# LPCB219_-_REMOTE_ACCEL_IF.net
KiCad netlist of a schematic drawn in Altium Designer
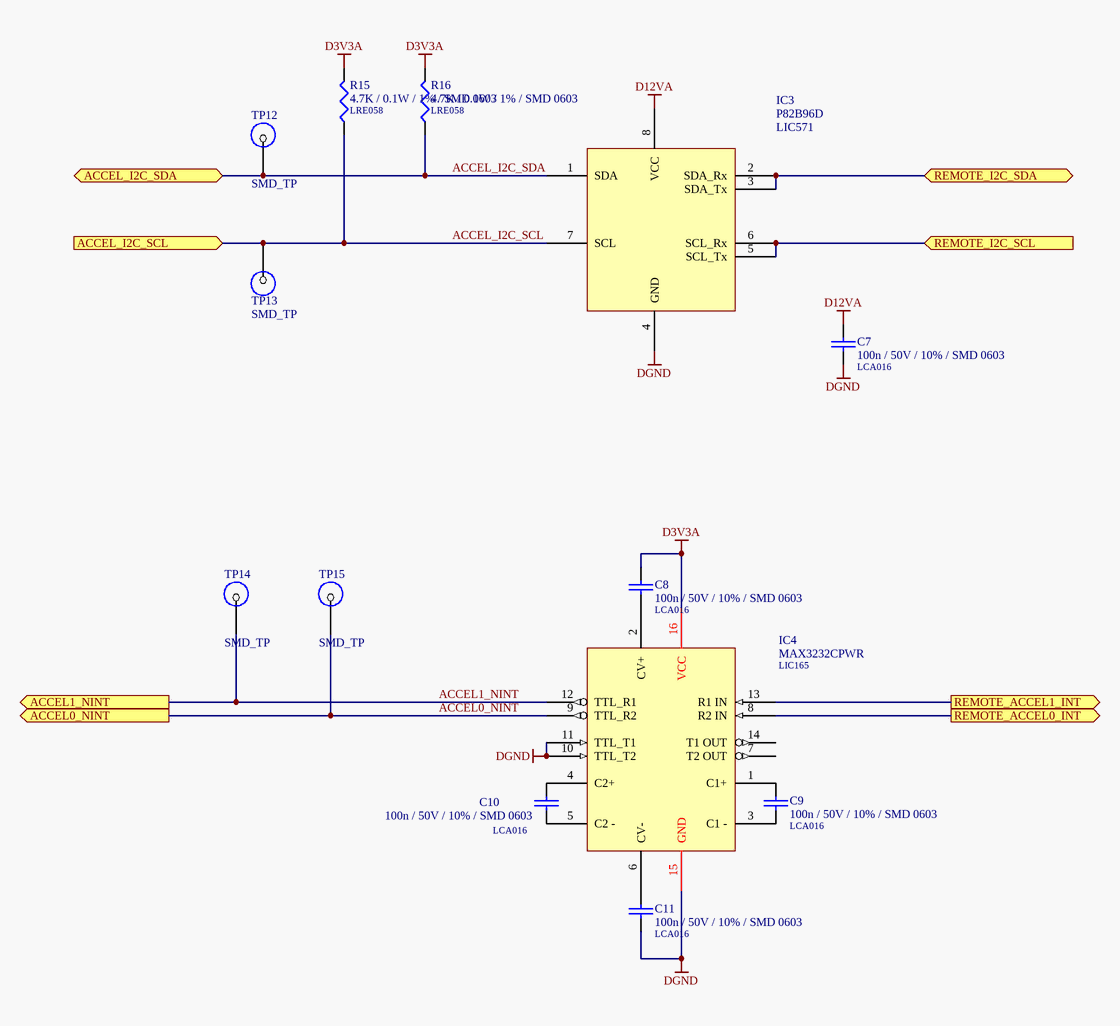
[diagram p0: LPCB219 - REMOTE ACCEL IF.SchDoc]

(export (version "E")
  (design (tool "Eeschema 10.0.6"))
  (components
    (comp (ref "C7")
      (value "100n / 50V / 10% / SMD 0603")
      (footprint "LFP011__CC1608-0603-IPC7351_B")
      (description "Capacitor, Ceramic Chip, 100nF (0.1uF), 50V, 5%, SMD 0603 [LCA016]")
      (fields (field (name "LDL_NUMBER") "LCA016"))
      (libsource (lib "LDL_Capacitors") (part "100n / 50V / 10% / SMD 0603"))
    )
    (comp (ref "C8")
      (value "100n / 50V / 10% / SMD 0603")
      (footprint "LFP011__CC1608-0603-IPC7351_B")
      (description "Capacitor, Ceramic Chip, 100nF, 50V, 10%, SMD 0603")
      (fields (field (name "LDL_NUMBER") "LCA016"))
      (libsource (lib "LDL_Capacitors") (part "100n / 50V / 10% / SMD 0603"))
    )
    (comp (ref "C9")
      (value "100n / 50V / 10% / SMD 0603")
      (footprint "LFP011__CC1608-0603-IPC7351_B")
      (description "Capacitor, Ceramic Chip, 100nF, 50V, 10%, SMD 0603")
      (fields (field (name "LDL_NUMBER") "LCA016"))
      (libsource (lib "LDL_Capacitors") (part "100n / 50V / 10% / SMD 0603"))
    )
    (comp (ref "C10")
      (value "100n / 50V / 10% / SMD 0603")
      (footprint "LFP011__CC1608-0603-IPC7351_B")
      (description "Capacitor, Ceramic Chip, 100nF, 50V, 10%, SMD 0603")
      (fields (field (name "LDL_NUMBER") "LCA016"))
      (libsource (lib "LDL_Capacitors") (part "100n / 50V / 10% / SMD 0603"))
    )
    (comp (ref "C11")
      (value "100n / 50V / 10% / SMD 0603")
      (footprint "LFP011__CC1608-0603-IPC7351_B")
      (description "Capacitor, Ceramic Chip, 100nF, 50V, 10%, SMD 0603")
      (fields (field (name "LDL_NUMBER") "LCA016"))
      (libsource (lib "LDL_Capacitors") (part "100n / 50V / 10% / SMD 0603"))
    )
    (comp (ref "IC3")
      (value "P82B96D")
      (footprint "LFP097__SOIC150-8")
      (description "IC, I2C Line Driver [LIC571]")
      (fields (field (name "LDL_NUMBER") "LIC571"))
      (libsource (lib "LDL_Semiconductors") (part "P82B96D"))
    )
    (comp (ref "IC4")
      (value "MAX3232CPWR")
      (footprint "LFP049__TSSOP-16")
      (description "IC, RS232 Line Driver, 3.3V, SMD TSSOP16")
      (fields (field (name "LDL_NUMBER") "LIC165"))
      (libsource (lib "LDL_Semiconductors") (part "MAX3232CPWR"))
    )
    (comp (ref "R15")
      (value "4.7K / 0.1W / 1% / SMD 0603")
      (footprint "LFP020__CR1608-0603-IPC7351_B")
      (description "Resistor, Ceramic Chip, 4K7, 0.1W, 1%, SMD 0603 [LRE058]")
      (fields (field (name "LDL_NUMBER") "LRE058"))
      (libsource (lib "LDL_Resistors") (part "4.7K / 0.1W / 1% / SMD 0603"))
    )
    (comp (ref "R16")
      (value "4.7K / 0.1W / 1% / SMD 0603")
      (footprint "LFP020__CR1608-0603-IPC7351_B")
      (description "Resistor, Ceramic Chip, 4K7, 0.1W, 1%, SMD 0603 [LRE058]")
      (fields (field (name "LDL_NUMBER") "LRE058"))
      (libsource (lib "LDL_Resistors") (part "4.7K / 0.1W / 1% / SMD 0603"))
    )
    (comp (ref "TP12")
      (value "SMD_TP")
      (footprint "SMD-TP")
      (description "SMD Test Point")
      (libsource (lib "LDL_Connectors") (part "SMD_TP"))
    )
    (comp (ref "TP13")
      (value "SMD_TP")
      (footprint "SMD-TP")
      (description "SMD Test Point")
      (libsource (lib "LDL_Connectors") (part "SMD_TP"))
    )
    (comp (ref "TP14")
      (value "SMD_TP")
      (footprint "SMD-TP")
      (description "SMD Test Point")
      (libsource (lib "LDL_Connectors") (part "SMD_TP"))
    )
    (comp (ref "TP15")
      (value "SMD_TP")
      (footprint "SMD-TP")
      (description "SMD Test Point")
      (libsource (lib "LDL_Connectors") (part "SMD_TP"))
    )
  )
  (nets
    (net (code "1") (name "/ACCEL0_NINT") (class "Default")
      (node (ref "IC4") (pin "9") (pinfunction "TTL_R2_9") (pintype "output"))
      (node (ref "TP15") (pin "1") (pintype "passive"))
    )
    (net (code "2") (name "/ACCEL1_NINT") (class "Default")
      (node (ref "IC4") (pin "12") (pinfunction "TTL_R1_12") (pintype "output"))
      (node (ref "TP14") (pin "1") (pintype "passive"))
    )
    (net (code "3") (name "/ACCEL_I2C_SCL") (class "Default")
      (node (ref "IC3") (pin "7") (pinfunction "SCL_7") (pintype "passive"))
      (node (ref "R15") (pin "1") (pintype "passive"))
      (node (ref "TP13") (pin "1") (pintype "passive"))
    )
    (net (code "4") (name "/ACCEL_I2C_SDA") (class "Default")
      (node (ref "IC3") (pin "1") (pinfunction "SDA_1") (pintype "passive"))
      (node (ref "R16") (pin "1") (pintype "passive"))
      (node (ref "TP12") (pin "1") (pintype "passive"))
    )
    (net (code "5") (name "/REMOTE_ACCEL0_INT") (class "Default")
      (node (ref "IC4") (pin "8") (pinfunction "R2_IN_8") (pintype "input"))
    )
    (net (code "6") (name "/REMOTE_ACCEL1_INT") (class "Default")
      (node (ref "IC4") (pin "13") (pinfunction "R1_IN_13") (pintype "input"))
    )
    (net (code "7") (name "/REMOTE_I2C_SCL") (class "Default")
      (node (ref "IC3") (pin "5") (pinfunction "SCL_Tx_5") (pintype "passive"))
      (node (ref "IC3") (pin "6") (pinfunction "SCL_Rx_6") (pintype "passive"))
    )
    (net (code "8") (name "/REMOTE_I2C_SDA") (class "Default")
      (node (ref "IC3") (pin "2") (pinfunction "SDA_Rx_2") (pintype "passive"))
      (node (ref "IC3") (pin "3") (pinfunction "SDA_Tx_3") (pintype "passive"))
    )
    (net (code "9") (name "D3V3A") (class "Default")
      (node (ref "C8") (pin "1") (pintype "passive"))
      (node (ref "IC4") (pin "16") (pinfunction "VCC_16") (pintype "power_in"))
      (node (ref "R15") (pin "2") (pintype "passive"))
      (node (ref "R16") (pin "2") (pintype "passive"))
    )
    (net (code "10") (name "D12VA") (class "Default")
      (node (ref "C7") (pin "1") (pintype "passive"))
      (node (ref "IC3") (pin "8") (pinfunction "VCC_8") (pintype "power_in"))
    )
    (net (code "11") (name "DGND") (class "Default")
      (node (ref "C11") (pin "2") (pintype "passive"))
      (node (ref "C7") (pin "2") (pintype "passive"))
      (node (ref "IC3") (pin "4") (pinfunction "GND_4") (pintype "power_in"))
      (node (ref "IC4") (pin "10") (pinfunction "TTL_T2_10") (pintype "input"))
      (node (ref "IC4") (pin "11") (pinfunction "TTL_T1_11") (pintype "input"))
      (node (ref "IC4") (pin "15") (pinfunction "GND_15") (pintype "power_in"))
    )
    (net (code "12") (name "Net-(IC4-C1+)") (class "Default")
      (node (ref "C9") (pin "1") (pintype "passive"))
      (node (ref "IC4") (pin "1") (pinfunction "C1+_1") (pintype "passive"))
    )
    (net (code "13") (name "Net-(IC4-C1_-)") (class "Default")
      (node (ref "C9") (pin "2") (pintype "passive"))
      (node (ref "IC4") (pin "3") (pinfunction "C1_-_3") (pintype "passive"))
    )
    (net (code "14") (name "Net-(IC4-C2+)") (class "Default")
      (node (ref "C10") (pin "1") (pintype "passive"))
      (node (ref "IC4") (pin "4") (pinfunction "C2+_4") (pintype "passive"))
    )
    (net (code "15") (name "Net-(IC4-C2_-)") (class "Default")
      (node (ref "C10") (pin "2") (pintype "passive"))
      (node (ref "IC4") (pin "5") (pinfunction "C2_-_5") (pintype "passive"))
    )
    (net (code "16") (name "Net-(IC4-CV+)") (class "Default")
      (node (ref "C8") (pin "2") (pintype "passive"))
      (node (ref "IC4") (pin "2") (pinfunction "CV+_2") (pintype "passive"))
    )
    (net (code "17") (name "Net-(IC4-CV-)") (class "Default")
      (node (ref "C11") (pin "1") (pintype "passive"))
      (node (ref "IC4") (pin "6") (pinfunction "CV-_6") (pintype "passive"))
    )
    (net (code "18") (name "unconnected-(IC4-T1_OUT-Pad14)") (class "Default")
      (node (ref "IC4") (pin "14") (pinfunction "T1_OUT_14") (pintype "output"))
    )
    (net (code "19") (name "unconnected-(IC4-T2_OUT-Pad7)") (class "Default")
      (node (ref "IC4") (pin "7") (pinfunction "T2_OUT_7") (pintype "output"))
    )
  )
)
